# 05-Switch_SFP_CM4_RJ45.net
KiCad netlist of a schematic drawn in Altium Designer
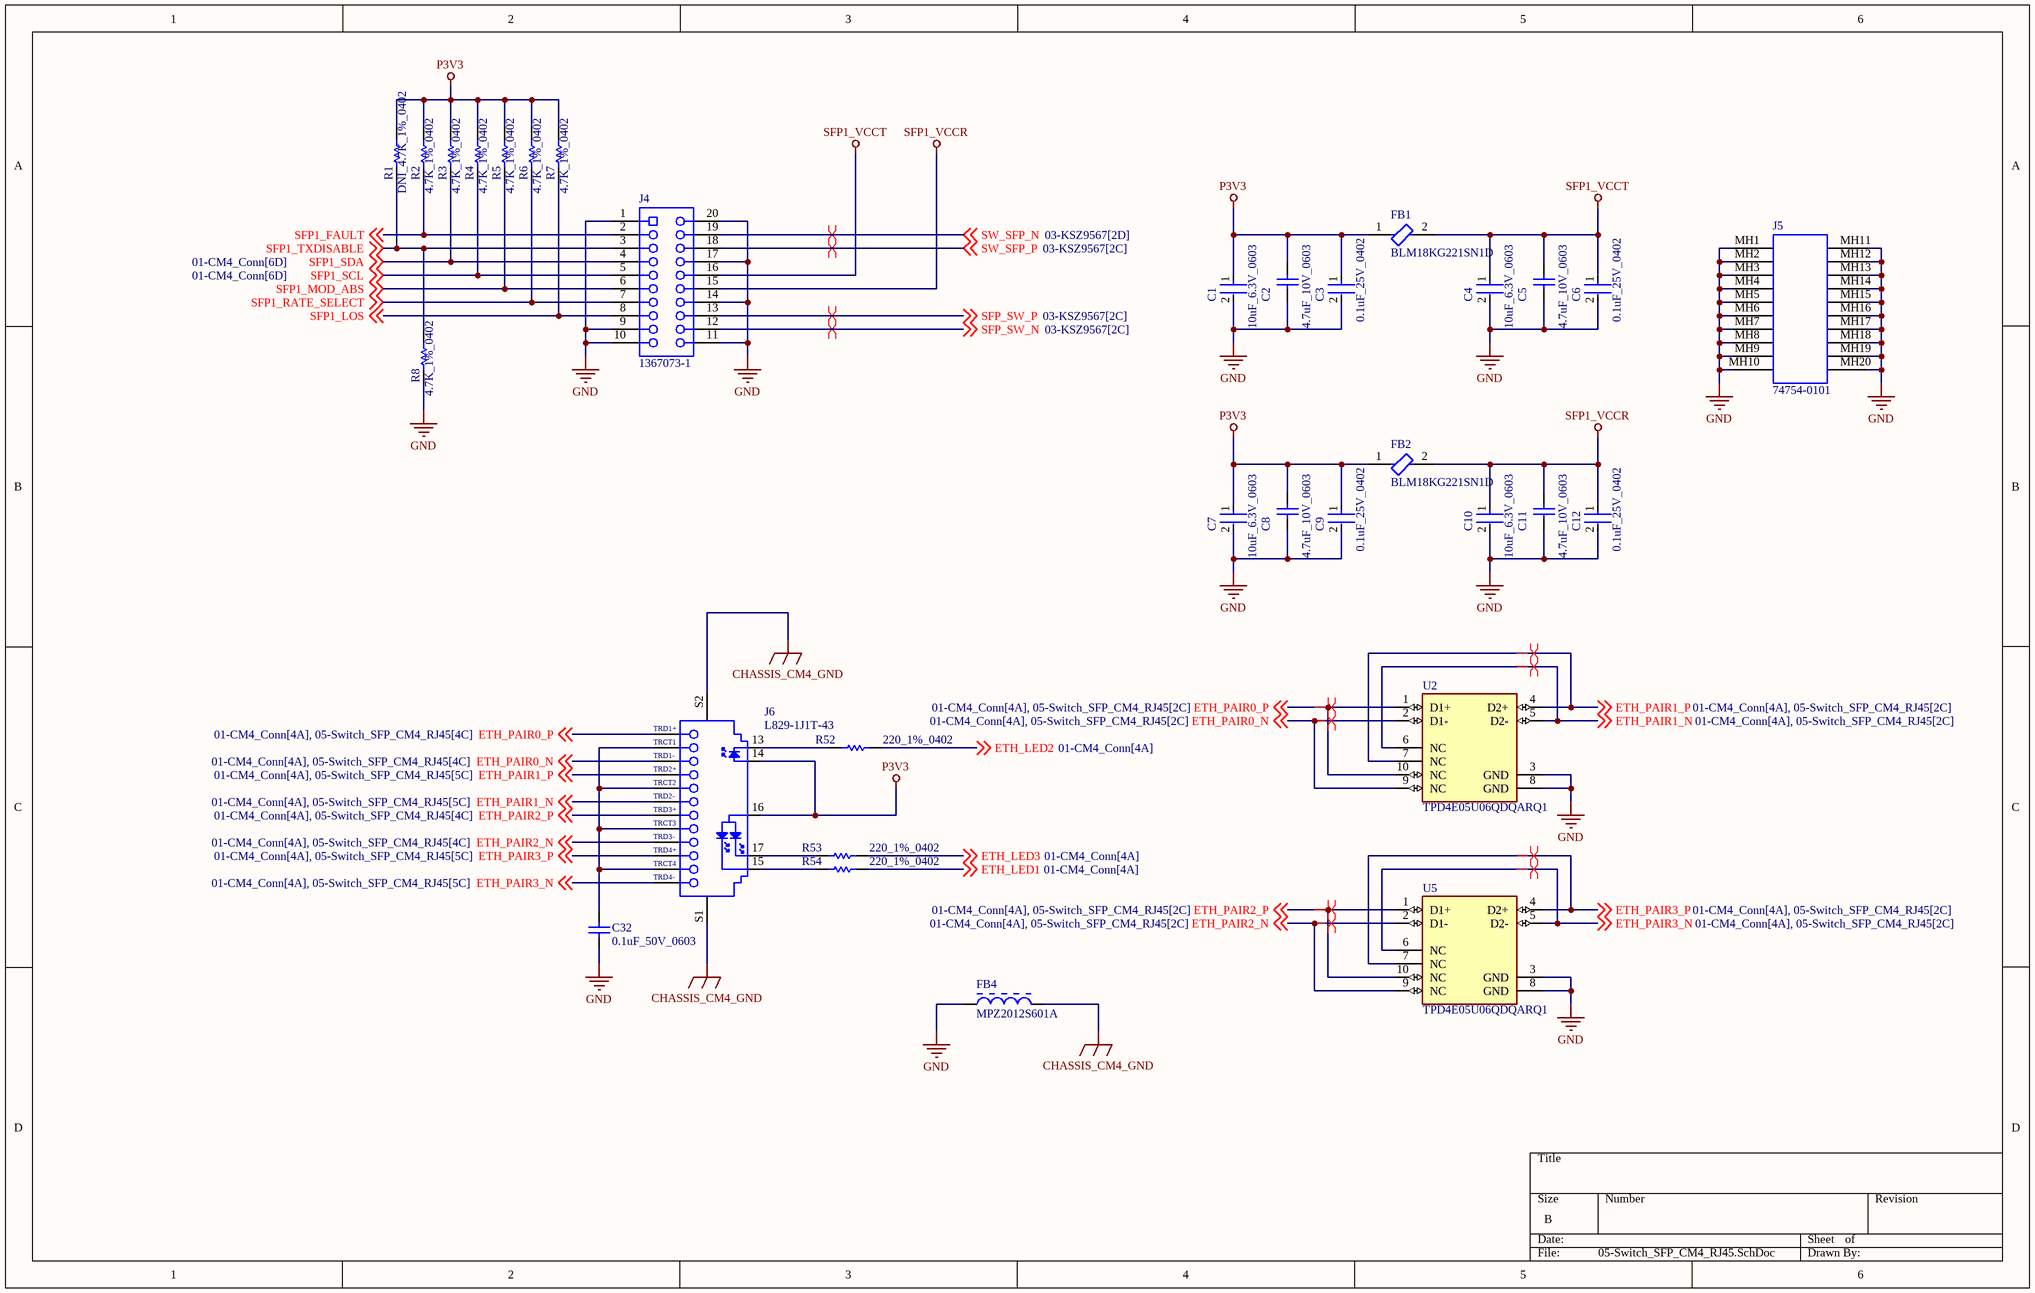
[diagram p0: 05-Switch_SFP_CM4_RJ45.SchDoc]

(export (version "E")
  (design (tool "Eeschema 10.0.6"))
  (components
    (comp (ref "C1")
      (value "10uF_6.3V_0603")
      (footprint "FP-C0603C106M9PACTU-MFG")
      (description "CAP CER 10UF 6.3V X5R 0603")
      (fields
        (field (name "MANUFACTURER PART NUMBER") "C0603C106M9PACTU")
        (field (name "MANUFACTURER") "Kemet")
      )
      (libsource (lib "Altium Content Vault") (part "b4654b650e69147ec39a6b967a45e02"))
    )
    (comp (ref "C2")
      (value "4.7uF_10V_0603")
      (footprint "CAPC1608X87X35NL15T15")
      (fields (field (name "PART NUMBER") "C0603C475K8PACTU") (field (name "MANUFACTURER") "Kemet"))
      (libsource (lib "Altium Content Vault") (part "CAP"))
    )
    (comp (ref "C3")
      (value "0.1uF_25V_0402")
      (footprint "FP-0402-L_1_0_1-W_0_5_0_1-IPC_C")
      (description "General Purpose Ceramic Capacitor, 0402, 100nF, 10%, X7R, 15%, 25V")
      (fields (field (name "VOLTAGE") "25V") (field (name "TOLERANCE") "10%"))
      (libsource (lib "Altium Content Vault") (part "b4654b650e69147ec39a6b967a45e02"))
    )
    (comp (ref "C4")
      (value "10uF_6.3V_0603")
      (footprint "FP-C0603C106M9PACTU-MFG")
      (description "CAP CER 10UF 6.3V X5R 0603")
      (fields
        (field (name "MANUFACTURER PART NUMBER") "C0603C106M9PACTU")
        (field (name "MANUFACTURER") "Kemet")
      )
      (libsource (lib "Altium Content Vault") (part "b4654b650e69147ec39a6b967a45e02"))
    )
    (comp (ref "C5")
      (value "4.7uF_10V_0603")
      (footprint "CAPC1608X87X35NL15T15")
      (fields (field (name "PART NUMBER") "C0603C475K8PACTU") (field (name "MANUFACTURER") "Kemet"))
      (libsource (lib "Altium Content Vault") (part "CAP"))
    )
    (comp (ref "C6")
      (value "0.1uF_25V_0402")
      (footprint "FP-0402-L_1_0_1-W_0_5_0_1-IPC_C")
      (description "General Purpose Ceramic Capacitor, 0402, 100nF, 10%, X7R, 15%, 25V")
      (fields (field (name "VOLTAGE") "25V") (field (name "TOLERANCE") "10%"))
      (libsource (lib "Altium Content Vault") (part "b4654b650e69147ec39a6b967a45e02"))
    )
    (comp (ref "C7")
      (value "10uF_6.3V_0603")
      (footprint "FP-C0603C106M9PACTU-MFG")
      (description "CAP CER 10UF 6.3V X5R 0603")
      (fields
        (field (name "MANUFACTURER PART NUMBER") "C0603C106M9PACTU")
        (field (name "MANUFACTURER") "Kemet")
      )
      (libsource (lib "Altium Content Vault") (part "b4654b650e69147ec39a6b967a45e02"))
    )
    (comp (ref "C8")
      (value "4.7uF_10V_0603")
      (footprint "CAPC1608X87X35NL15T15")
      (fields (field (name "PART NUMBER") "C0603C475K8PACTU") (field (name "MANUFACTURER") "Kemet"))
      (libsource (lib "Altium Content Vault") (part "CAP"))
    )
    (comp (ref "C9")
      (value "0.1uF_25V_0402")
      (footprint "FP-0402-L_1_0_1-W_0_5_0_1-IPC_C")
      (description "General Purpose Ceramic Capacitor, 0402, 100nF, 10%, X7R, 15%, 25V")
      (fields (field (name "VOLTAGE") "25V") (field (name "TOLERANCE") "10%"))
      (libsource (lib "Altium Content Vault") (part "b4654b650e69147ec39a6b967a45e02"))
    )
    (comp (ref "C10")
      (value "10uF_6.3V_0603")
      (footprint "FP-C0603C106M9PACTU-MFG")
      (description "CAP CER 10UF 6.3V X5R 0603")
      (fields
        (field (name "MANUFACTURER PART NUMBER") "C0603C106M9PACTU")
        (field (name "MANUFACTURER") "Kemet")
      )
      (libsource (lib "Altium Content Vault") (part "b4654b650e69147ec39a6b967a45e02"))
    )
    (comp (ref "C11")
      (value "4.7uF_10V_0603")
      (footprint "CAPC1608X87X35NL15T15")
      (fields (field (name "PART NUMBER") "C0603C475K8PACTU") (field (name "MANUFACTURER") "Kemet"))
      (libsource (lib "Altium Content Vault") (part "CAP"))
    )
    (comp (ref "C12")
      (value "0.1uF_25V_0402")
      (footprint "FP-0402-L_1_0_1-W_0_5_0_1-IPC_C")
      (description "General Purpose Ceramic Capacitor, 0402, 100nF, 10%, X7R, 15%, 25V")
      (fields (field (name "VOLTAGE") "25V") (field (name "TOLERANCE") "10%"))
      (libsource (lib "Altium Content Vault") (part "b4654b650e69147ec39a6b967a45e02"))
    )
    (comp (ref "C32")
      (value "0.1uF_50V_0603")
      (footprint "CAPC1608X90X35ML10T15")
      (description "Chip Capacitor, 0.1 uF, +/- 10%, 50 V, -55 to 125 degC, 0603 (1608 Metric), RoHS, Tape and Reel")
      (fields (field (name "TOLERANCE") "10%") (field (name "VOLTAGE") "50V"))
      (libsource (lib "Altium Content Vault") (part "CAP-NP-2"))
    )
    (comp (ref "FB1")
      (value "BLM18KG221SN1D")
      (footprint "FP-BLM18-0_15-t0_8-IPC_B")
      (description "Chip Ferrite Bead, 0603, 220Ω @ 100MHz, 0.05Ω, 25%, 2.2A")
      (fields (field (name "TOLERANCE") "25%"))
      (libsource (lib "Altium Content Vault") (part "5f30dd21d616792df468990f7003faa"))
    )
    (comp (ref "FB2")
      (value "BLM18KG221SN1D")
      (footprint "FP-BLM18-0_15-t0_8-IPC_B")
      (description "Chip Ferrite Bead, 0603, 220Ω @ 100MHz, 0.05Ω, 25%, 2.2A")
      (fields (field (name "TOLERANCE") "25%"))
      (libsource (lib "Altium Content Vault") (part "5f30dd21d616792df468990f7003faa"))
    )
    (comp (ref "FB4")
      (value "MPZ2012S601A")
      (footprint "TDK-MPZ2012_V")
      (fields (field (name "TOLERANCE") "25%") (field (name "MANUFACTURER") "TDK"))
      (libsource (lib "Altium Content Vault") (part "BEAD-2"))
    )
    (comp (ref "J4")
      (value "1367073-1")
      (footprint "TECO-1367073-1_V")
      (fields (field (name "MANUFACTURER") "TE Connectivity"))
      (libsource (lib "Altium Content Vault") (part "CN-2P-F-R20_B"))
    )
    (comp (ref "J5")
      (value "74754-0101")
      (footprint "MOLX-74754-0101_V")
      (description "SFP+ Cage, Single Port, Height 10.85 mm, Tail Height 3.05 mm, -40 to 85 degC, RoHS, Tray")
      (libsource (lib "Altium Content Vault") (part "MOLX-74754-0101"))
    )
    (comp (ref "J6")
      (value "L829-1J1T-43")
      (footprint "BELS-L829-1J1T-43_V")
      (description "Gigabit MagJack(R) Ultra Low Profile, 10/100/1000 Base-T, 19-Pin THD, RoHS, Tray")
      (libsource (lib "Altium Content Vault") (part "RJ45-17-2SHLD"))
    )
    (comp (ref "R1")
      (value "DNI_4.7K_1%_0402")
      (footprint "RESC1005X40X25NL10T10")
      (fields (field (name "MANUFACTURER") "Bourns") (field (name "PART NUMBER") "CR0402-FX-4701GLF"))
      (libsource (lib "Altium Content Vault") (part "RES"))
    )
    (comp (ref "R2")
      (value "4.7K_1%_0402")
      (footprint "RESC1005X40X25NL10T10")
      (fields (field (name "MANUFACTURER") "Bourns") (field (name "PART NUMBER") "CR0402-FX-4701GLF"))
      (libsource (lib "Altium Content Vault") (part "RES"))
    )
    (comp (ref "R3")
      (value "4.7K_1%_0402")
      (footprint "RESC1005X40X25NL10T10")
      (fields (field (name "MANUFACTURER") "Bourns") (field (name "PART NUMBER") "CR0402-FX-4701GLF"))
      (libsource (lib "Altium Content Vault") (part "RES"))
    )
    (comp (ref "R4")
      (value "4.7K_1%_0402")
      (footprint "RESC1005X40X25NL10T10")
      (fields (field (name "MANUFACTURER") "Bourns") (field (name "PART NUMBER") "CR0402-FX-4701GLF"))
      (libsource (lib "Altium Content Vault") (part "RES"))
    )
    (comp (ref "R5")
      (value "4.7K_1%_0402")
      (footprint "RESC1005X40X25NL10T10")
      (fields (field (name "MANUFACTURER") "Bourns") (field (name "PART NUMBER") "CR0402-FX-4701GLF"))
      (libsource (lib "Altium Content Vault") (part "RES"))
    )
    (comp (ref "R6")
      (value "4.7K_1%_0402")
      (footprint "RESC1005X40X25NL10T10")
      (fields (field (name "MANUFACTURER") "Bourns") (field (name "PART NUMBER") "CR0402-FX-4701GLF"))
      (libsource (lib "Altium Content Vault") (part "RES"))
    )
    (comp (ref "R7")
      (value "4.7K_1%_0402")
      (footprint "RESC1005X40X25NL10T10")
      (fields (field (name "MANUFACTURER") "Bourns") (field (name "PART NUMBER") "CR0402-FX-4701GLF"))
      (libsource (lib "Altium Content Vault") (part "RES"))
    )
    (comp (ref "R8")
      (value "4.7K_1%_0402")
      (footprint "RESC1005X40X25NL10T10")
      (fields (field (name "MANUFACTURER") "Bourns") (field (name "PART NUMBER") "CR0402-FX-4701GLF"))
      (libsource (lib "Altium Content Vault") (part "RES"))
    )
    (comp (ref "R52")
      (value "220_1%_0402")
      (footprint "RESC1005X40X25NL05T10")
      (fields (field (name "MANUFACTURER") "Yageo / Phycomp") (field (name "PART NUMBER") "RC0402JR-07220RL"))
      (libsource (lib "Altium Content Vault") (part "RES"))
    )
    (comp (ref "R53")
      (value "220_1%_0402")
      (footprint "RESC1005X40X25NL05T10")
      (fields (field (name "MANUFACTURER") "Yageo / Phycomp") (field (name "PART NUMBER") "RC0402JR-07220RL"))
      (libsource (lib "Altium Content Vault") (part "RES"))
    )
    (comp (ref "R54")
      (value "220_1%_0402")
      (footprint "RESC1005X40X25NL05T10")
      (fields (field (name "MANUFACTURER") "Yageo / Phycomp") (field (name "PART NUMBER") "RC0402JR-07220RL"))
      (libsource (lib "Altium Content Vault") (part "RES"))
    )
    (comp (ref "U2")
      (value "TPD4E05U06QDQARQ1")
      (footprint "FP-DQA0010A-MFG")
      (description "TVS DIODE 5.5V 14V 10USON")
      (fields
        (field (name "OCTOPART") "https://octopart.com/tpd4e05u06qdqarq1-texas+instruments-48523459")
        (field (name "MANUFACTURER") "Texas Instruments")
      )
      (libsource (lib "Altium Content Vault") (part "f11f7ff102fa2b028e1355c732c836d"))
    )
    (comp (ref "U5")
      (value "TPD4E05U06QDQARQ1")
      (footprint "FP-DQA0010A-MFG")
      (description "TVS DIODE 5.5V 14V 10USON")
      (fields
        (field (name "OCTOPART") "https://octopart.com/tpd4e05u06qdqarq1-texas+instruments-48523459")
        (field (name "MANUFACTURER") "Texas Instruments")
      )
      (libsource (lib "Altium Content Vault") (part "f11f7ff102fa2b028e1355c732c836d"))
    )
  )
  (nets
    (net (code "1") (name "CHASSIS_CM4_GND") (class "Default")
      (node (ref "FB4") (pin "2") (pinfunction "2_2") (pintype "passive"))
      (node (ref "J6") (pin "S1") (pinfunction "S1_S1") (pintype "passive"))
      (node (ref "J6") (pin "S2") (pinfunction "S2_S2") (pintype "passive"))
    )
    (net (code "2") (name "ETH_LED1") (class "Default")
      (node (ref "R54") (pin "2") (pinfunction "2_2") (pintype "passive"))
    )
    (net (code "3") (name "ETH_LED2") (class "Default")
      (node (ref "R52") (pin "2") (pinfunction "2_2") (pintype "passive"))
    )
    (net (code "4") (name "ETH_LED3") (class "Default")
      (node (ref "R53") (pin "2") (pinfunction "2_2") (pintype "passive"))
    )
    (net (code "5") (name "ETH_PAIR0_N") (class "Default")
      (node (ref "J6") (pin "3") (pinfunction "TRD1-_3") (pintype "passive"))
      (node (ref "U2") (pin "2") (pinfunction "D1-_2") (pintype "bidirectional"))
      (node (ref "U2") (pin "9") (pinfunction "NC_9") (pintype "bidirectional"))
    )
    (net (code "6") (name "ETH_PAIR0_P") (class "Default")
      (node (ref "J6") (pin "1") (pinfunction "TRD1+_1") (pintype "passive"))
      (node (ref "U2") (pin "1") (pinfunction "D1+_1") (pintype "bidirectional"))
      (node (ref "U2") (pin "10") (pinfunction "NC_10") (pintype "bidirectional"))
    )
    (net (code "7") (name "ETH_PAIR1_N") (class "Default")
      (node (ref "J6") (pin "6") (pinfunction "TRD2-_6") (pintype "passive"))
      (node (ref "U2") (pin "5") (pinfunction "D2-_5") (pintype "bidirectional"))
      (node (ref "U2") (pin "6") (pinfunction "NC_6") (pintype "passive"))
    )
    (net (code "8") (name "ETH_PAIR1_P") (class "Default")
      (node (ref "J6") (pin "4") (pinfunction "TRD2+_4") (pintype "passive"))
      (node (ref "U2") (pin "4") (pinfunction "D2+_4") (pintype "bidirectional"))
      (node (ref "U2") (pin "7") (pinfunction "NC_7") (pintype "passive"))
    )
    (net (code "9") (name "ETH_PAIR2_N") (class "Default")
      (node (ref "J6") (pin "9") (pinfunction "TRD3-_9") (pintype "passive"))
      (node (ref "U5") (pin "2") (pinfunction "D1-_2") (pintype "bidirectional"))
      (node (ref "U5") (pin "9") (pinfunction "NC_9") (pintype "bidirectional"))
    )
    (net (code "10") (name "ETH_PAIR2_P") (class "Default")
      (node (ref "J6") (pin "7") (pinfunction "TRD3+_7") (pintype "passive"))
      (node (ref "U5") (pin "1") (pinfunction "D1+_1") (pintype "bidirectional"))
      (node (ref "U5") (pin "10") (pinfunction "NC_10") (pintype "bidirectional"))
    )
    (net (code "11") (name "ETH_PAIR3_N") (class "Default")
      (node (ref "J6") (pin "12") (pinfunction "TRD4-_12") (pintype "passive"))
      (node (ref "U5") (pin "5") (pinfunction "D2-_5") (pintype "bidirectional"))
      (node (ref "U5") (pin "6") (pinfunction "NC_6") (pintype "passive"))
    )
    (net (code "12") (name "ETH_PAIR3_P") (class "Default")
      (node (ref "J6") (pin "10") (pinfunction "TRD4+_10") (pintype "passive"))
      (node (ref "U5") (pin "4") (pinfunction "D2+_4") (pintype "bidirectional"))
      (node (ref "U5") (pin "7") (pinfunction "NC_7") (pintype "passive"))
    )
    (net (code "13") (name "GND") (class "Default")
      (node (ref "C1") (pin "2") (pinfunction "2_2") (pintype "passive"))
      (node (ref "C10") (pin "2") (pinfunction "2_2") (pintype "passive"))
      (node (ref "C11") (pin "1") (pinfunction "1_1") (pintype "passive"))
      (node (ref "C12") (pin "2") (pinfunction "2_2") (pintype "passive"))
      (node (ref "C2") (pin "1") (pinfunction "1_1") (pintype "passive"))
      (node (ref "C3") (pin "2") (pinfunction "2_2") (pintype "passive"))
      (node (ref "C32") (pin "1") (pinfunction "1_1") (pintype "passive"))
      (node (ref "C4") (pin "2") (pinfunction "2_2") (pintype "passive"))
      (node (ref "C5") (pin "1") (pinfunction "1_1") (pintype "passive"))
      (node (ref "C6") (pin "2") (pinfunction "2_2") (pintype "passive"))
      (node (ref "C7") (pin "2") (pinfunction "2_2") (pintype "passive"))
      (node (ref "C8") (pin "1") (pinfunction "1_1") (pintype "passive"))
      (node (ref "C9") (pin "2") (pinfunction "2_2") (pintype "passive"))
      (node (ref "FB4") (pin "1") (pinfunction "1_1") (pintype "passive"))
      (node (ref "J4") (pin "1") (pinfunction "1_1") (pintype "passive"))
      (node (ref "J4") (pin "10") (pinfunction "10_10") (pintype "passive"))
      (node (ref "J4") (pin "11") (pinfunction "11_11") (pintype "passive"))
      (node (ref "J4") (pin "14") (pinfunction "14_14") (pintype "passive"))
      (node (ref "J4") (pin "17") (pinfunction "17_17") (pintype "passive"))
      (node (ref "J4") (pin "20") (pinfunction "20_20") (pintype "passive"))
      (node (ref "J4") (pin "9") (pinfunction "9_9") (pintype "passive"))
      (node (ref "J5") (pin "MH1") (pinfunction "MH1_MH1") (pintype "passive"))
      (node (ref "J5") (pin "MH10") (pinfunction "MH10_MH10") (pintype "passive"))
      (node (ref "J5") (pin "MH11") (pinfunction "MH11_MH11") (pintype "passive"))
      (node (ref "J5") (pin "MH12") (pinfunction "MH12_MH12") (pintype "passive"))
      (node (ref "J5") (pin "MH13") (pinfunction "MH13_MH13") (pintype "passive"))
      (node (ref "J5") (pin "MH14") (pinfunction "MH14_MH14") (pintype "passive"))
      (node (ref "J5") (pin "MH15") (pinfunction "MH15_MH15") (pintype "passive"))
      (node (ref "J5") (pin "MH16") (pinfunction "MH16_MH16") (pintype "passive"))
      (node (ref "J5") (pin "MH17") (pinfunction "MH17_MH17") (pintype "passive"))
      (node (ref "J5") (pin "MH18") (pinfunction "MH18_MH18") (pintype "passive"))
      (node (ref "J5") (pin "MH19") (pinfunction "MH19_MH19") (pintype "passive"))
      (node (ref "J5") (pin "MH2") (pinfunction "MH2_MH2") (pintype "passive"))
      (node (ref "J5") (pin "MH20") (pinfunction "MH20_MH20") (pintype "passive"))
      (node (ref "J5") (pin "MH3") (pinfunction "MH3_MH3") (pintype "passive"))
      (node (ref "J5") (pin "MH4") (pinfunction "MH4_MH4") (pintype "passive"))
      (node (ref "J5") (pin "MH5") (pinfunction "MH5_MH5") (pintype "passive"))
      (node (ref "J5") (pin "MH6") (pinfunction "MH6_MH6") (pintype "passive"))
      (node (ref "J5") (pin "MH7") (pinfunction "MH7_MH7") (pintype "passive"))
      (node (ref "J5") (pin "MH8") (pinfunction "MH8_MH8") (pintype "passive"))
      (node (ref "J5") (pin "MH9") (pinfunction "MH9_MH9") (pintype "passive"))
      (node (ref "R8") (pin "2") (pinfunction "2_2") (pintype "passive"))
      (node (ref "U2") (pin "3") (pinfunction "GND_3") (pintype "power_in"))
      (node (ref "U2") (pin "8") (pinfunction "GND_8") (pintype "power_in"))
      (node (ref "U5") (pin "3") (pinfunction "GND_3") (pintype "power_in"))
      (node (ref "U5") (pin "8") (pinfunction "GND_8") (pintype "power_in"))
    )
    (net (code "14") (name "Net-(J6-Pad13)") (class "Default")
      (node (ref "J6") (pin "13") (pinfunction "13_13") (pintype "passive"))
      (node (ref "R52") (pin "1") (pinfunction "1_1") (pintype "passive"))
    )
    (net (code "15") (name "Net-(J6-Pad15)") (class "Default")
      (node (ref "J6") (pin "15") (pinfunction "15_15") (pintype "passive"))
      (node (ref "R54") (pin "1") (pinfunction "1_1") (pintype "passive"))
    )
    (net (code "16") (name "Net-(J6-Pad17)") (class "Default")
      (node (ref "J6") (pin "17") (pinfunction "17_17") (pintype "passive"))
      (node (ref "R53") (pin "1") (pinfunction "1_1") (pintype "passive"))
    )
    (net (code "17") (name "Net-(J6-TRCT1)") (class "Default")
      (node (ref "C32") (pin "2") (pinfunction "2_2") (pintype "passive"))
      (node (ref "J6") (pin "11") (pinfunction "TRCT4_11") (pintype "passive"))
      (node (ref "J6") (pin "2") (pinfunction "TRCT1_2") (pintype "passive"))
      (node (ref "J6") (pin "5") (pinfunction "TRCT2_5") (pintype "passive"))
      (node (ref "J6") (pin "8") (pinfunction "TRCT3_8") (pintype "passive"))
    )
    (net (code "18") (name "P3V3") (class "Default")
      (node (ref "C1") (pin "1") (pinfunction "1_1") (pintype "passive"))
      (node (ref "C2") (pin "2") (pinfunction "2_2") (pintype "passive"))
      (node (ref "C3") (pin "1") (pinfunction "1_1") (pintype "passive"))
      (node (ref "C7") (pin "1") (pinfunction "1_1") (pintype "passive"))
      (node (ref "C8") (pin "2") (pinfunction "2_2") (pintype "passive"))
      (node (ref "C9") (pin "1") (pinfunction "1_1") (pintype "passive"))
      (node (ref "FB1") (pin "1") (pinfunction "1_1") (pintype "passive"))
      (node (ref "FB2") (pin "1") (pinfunction "1_1") (pintype "passive"))
      (node (ref "J6") (pin "14") (pinfunction "14_14") (pintype "passive"))
      (node (ref "J6") (pin "16") (pinfunction "16_16") (pintype "passive"))
      (node (ref "R1") (pin "1") (pinfunction "1_1") (pintype "passive"))
      (node (ref "R2") (pin "1") (pinfunction "1_1") (pintype "passive"))
      (node (ref "R3") (pin "1") (pinfunction "1_1") (pintype "passive"))
      (node (ref "R4") (pin "1") (pinfunction "1_1") (pintype "passive"))
      (node (ref "R5") (pin "1") (pinfunction "1_1") (pintype "passive"))
      (node (ref "R6") (pin "1") (pinfunction "1_1") (pintype "passive"))
      (node (ref "R7") (pin "1") (pinfunction "1_1") (pintype "passive"))
    )
    (net (code "19") (name "SFP1_FAULT") (class "Default")
      (node (ref "J4") (pin "2") (pinfunction "2_2") (pintype "passive"))
      (node (ref "R2") (pin "2") (pinfunction "2_2") (pintype "passive"))
    )
    (net (code "20") (name "SFP1_LOS") (class "Default")
      (node (ref "J4") (pin "8") (pinfunction "8_8") (pintype "passive"))
      (node (ref "R7") (pin "2") (pinfunction "2_2") (pintype "passive"))
    )
    (net (code "21") (name "SFP1_MOD_ABS") (class "Default")
      (node (ref "J4") (pin "6") (pinfunction "6_6") (pintype "passive"))
      (node (ref "R5") (pin "2") (pinfunction "2_2") (pintype "passive"))
    )
    (net (code "22") (name "SFP1_RATE_SELECT") (class "Default")
      (node (ref "J4") (pin "7") (pinfunction "7_7") (pintype "passive"))
      (node (ref "R6") (pin "2") (pinfunction "2_2") (pintype "passive"))
    )
    (net (code "23") (name "SFP1_SCL") (class "Default")
      (node (ref "J4") (pin "5") (pinfunction "5_5") (pintype "passive"))
      (node (ref "R4") (pin "2") (pinfunction "2_2") (pintype "passive"))
    )
    (net (code "24") (name "SFP1_SDA") (class "Default")
      (node (ref "J4") (pin "4") (pinfunction "4_4") (pintype "passive"))
      (node (ref "R3") (pin "2") (pinfunction "2_2") (pintype "passive"))
    )
    (net (code "25") (name "SFP1_TXDISABLE") (class "Default")
      (node (ref "J4") (pin "3") (pinfunction "3_3") (pintype "passive"))
      (node (ref "R1") (pin "2") (pinfunction "2_2") (pintype "passive"))
      (node (ref "R8") (pin "1") (pinfunction "1_1") (pintype "passive"))
    )
    (net (code "26") (name "SFP1_VCCR") (class "Default")
      (node (ref "C10") (pin "1") (pinfunction "1_1") (pintype "passive"))
      (node (ref "C11") (pin "2") (pinfunction "2_2") (pintype "passive"))
      (node (ref "C12") (pin "1") (pinfunction "1_1") (pintype "passive"))
      (node (ref "FB2") (pin "2") (pinfunction "2_2") (pintype "passive"))
      (node (ref "J4") (pin "15") (pinfunction "15_15") (pintype "passive"))
    )
    (net (code "27") (name "SFP1_VCCT") (class "Default")
      (node (ref "C4") (pin "1") (pinfunction "1_1") (pintype "passive"))
      (node (ref "C5") (pin "2") (pinfunction "2_2") (pintype "passive"))
      (node (ref "C6") (pin "1") (pinfunction "1_1") (pintype "passive"))
      (node (ref "FB1") (pin "2") (pinfunction "2_2") (pintype "passive"))
      (node (ref "J4") (pin "16") (pinfunction "16_16") (pintype "passive"))
    )
    (net (code "28") (name "SFP_SW_N") (class "Default")
      (node (ref "J4") (pin "12") (pinfunction "12_12") (pintype "passive"))
    )
    (net (code "29") (name "SFP_SW_P") (class "Default")
      (node (ref "J4") (pin "13") (pinfunction "13_13") (pintype "passive"))
    )
    (net (code "30") (name "SW_SFP_N") (class "Default")
      (node (ref "J4") (pin "19") (pinfunction "19_19") (pintype "passive"))
    )
    (net (code "31") (name "SW_SFP_P") (class "Default")
      (node (ref "J4") (pin "18") (pinfunction "18_18") (pintype "passive"))
    )
  )
)
